# Regulador5V.net
KiCad netlist of a schematic drawn in Altium Designer
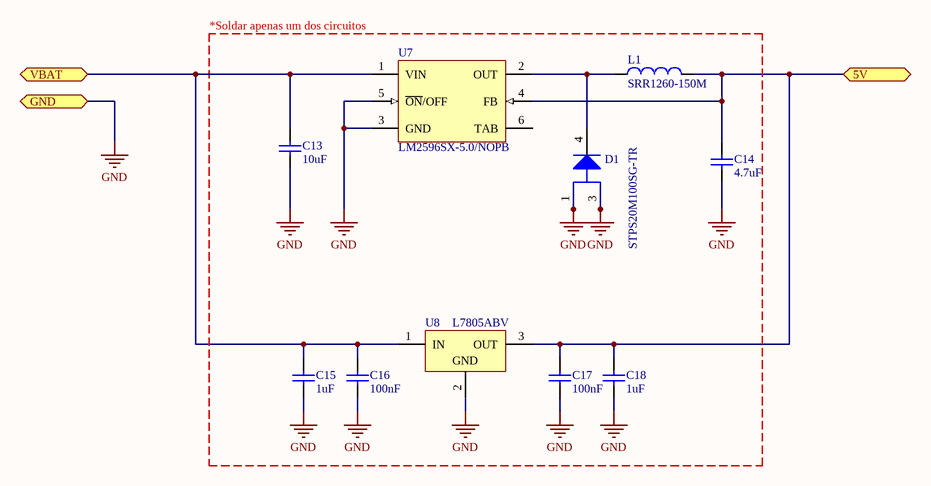
[diagram p0: Regulador5V.SchDoc]

(export (version "E")
  (design (tool "Eeschema 10.0.6"))
  (components
    (comp (ref "C13")
      (value "10uF")
      (footprint "CAPC1206(3216)190_N")
      (description "CAP 10uF 50V ±20% 1206 (3216 Metric) Thickness 1.9mm SMD")
      (fields (field (name "TOLERANCE") "Â±20%"))
      (libsource (lib "Altium Content Vault") (part "CAP"))
    )
    (comp (ref "C14")
      (value "4.7uF")
      (footprint "CAPC0805(2012)145_N")
      (description "CAP 4.7uF 25V ±20% 0805 (2012 Metric) Thickness 1.45mm SMD")
      (fields (field (name "TOLERANCE") "Â±20%"))
      (libsource (lib "Altium Content Vault") (part "CAP"))
    )
    (comp (ref "C15")
      (value "1uF")
      (footprint "CAPC0805(2012)145_L")
      (description "CAP 1uF 50V ±10% 0805 (2012 Metric) Thickness 1.45mm SMD")
      (fields (field (name "TOLERANCE") "Â±10%"))
      (libsource (lib "Altium Content Vault") (part "CAP"))
    )
    (comp (ref "C16")
      (value "100nF")
      (footprint "CAPC0805(2012)145_N")
      (description "CAP 100nF 50V ±5% 0805 (2012 Metric) Thickness 1.45mm SMD")
      (fields (field (name "TOLERANCE") "Â±5%"))
      (libsource (lib "Altium Content Vault") (part "CAP"))
    )
    (comp (ref "C17")
      (value "100nF")
      (footprint "CAPC0805(2012)145_N")
      (description "CAP 100nF 50V ±5% 0805 (2012 Metric) Thickness 1.45mm SMD")
      (fields (field (name "TOLERANCE") "Â±5%"))
      (libsource (lib "Altium Content Vault") (part "CAP"))
    )
    (comp (ref "C18")
      (value "1uF")
      (footprint "CAPC0805(2012)145_L")
      (description "CAP 1uF 50V ±10% 0805 (2012 Metric) Thickness 1.45mm SMD")
      (fields (field (name "TOLERANCE") "Â±10%"))
      (libsource (lib "Altium Content Vault") (part "CAP"))
    )
    (comp (ref "D1")
      (value "STPS20M100SG-TR")
      (footprint "ONSC-D2PAK-3-418B-04_J_V")
      (description "SWITCHMODE(TM) Power Rectifier ORing Function Diode, 3-Pin D2PAK, Tape and Reel")
      (fields (field (name "MANUFACTURER") "On Semiconductor"))
      (libsource (lib "Diodo D2PAK") (part "CMP-1055-00080-1"))
    )
    (comp (ref "L1")
      (value "SRR1260-150M")
      (footprint "BOUR-SRR1260_V")
      (description "Shielded Power Inductor, 15 uH, +/- 20%, -40 to 125 degC, 2-Pin SMD, RoHS, Tape and Reel")
      (fields (field (name "MANUFACTURER") "Bourns") (field (name "TOLERANCE") "20%"))
      (libsource (lib "Altium Content Vault") (part "IND-2"))
    )
    (comp (ref "U7")
      (value "LM2596SX-5.0/NOPB")
      (footprint "TS5B_M")
      (description "SIMPLE SWITCHER® Power Converter 150 KHz 3A Step-Down Voltage Regulator, 5-pin TO-263")
      (fields (field (name "MANUFACTURER") "Texas Instruments"))
      (libsource (lib "LM2596SX-5.0") (part "CMP-0069-00282-2"))
    )
    (comp (ref "U8")
      (value "L7805ABV")
      (footprint "TO220")
      (description "Positive Voltage Regulator, 5V, 3-Pin TO-220")
      (libsource (lib "Altium Content Vault") (part "PM-REG-L4940-SIL3"))
    )
  )
  (nets
    (net (code "1") (name "/5V") (class "Default")
      (node (ref "C14") (pin "2") (pinfunction "2_2") (pintype "passive"))
      (node (ref "C17") (pin "2") (pinfunction "2_2") (pintype "passive"))
      (node (ref "C18") (pin "2") (pinfunction "2_2") (pintype "passive"))
      (node (ref "L1") (pin "2") (pinfunction "2_2") (pintype "passive"))
      (node (ref "U7") (pin "4") (pinfunction "FB_4") (pintype "input"))
      (node (ref "U8") (pin "3") (pinfunction "OUT_3") (pintype "power_in"))
    )
    (net (code "2") (name "/VBAT") (class "Default")
      (node (ref "C13") (pin "2") (pinfunction "2_2") (pintype "passive"))
      (node (ref "C15") (pin "2") (pinfunction "2_2") (pintype "passive"))
      (node (ref "C16") (pin "2") (pinfunction "2_2") (pintype "passive"))
      (node (ref "U7") (pin "1") (pinfunction "VIN_1") (pintype "power_in"))
      (node (ref "U8") (pin "1") (pinfunction "IN_1") (pintype "power_in"))
    )
    (net (code "3") (name "GND") (class "Default")
      (node (ref "C13") (pin "1") (pinfunction "1_1") (pintype "passive"))
      (node (ref "C14") (pin "1") (pinfunction "1_1") (pintype "passive"))
      (node (ref "C15") (pin "1") (pinfunction "1_1") (pintype "passive"))
      (node (ref "C16") (pin "1") (pinfunction "1_1") (pintype "passive"))
      (node (ref "C17") (pin "1") (pinfunction "1_1") (pintype "passive"))
      (node (ref "C18") (pin "1") (pinfunction "1_1") (pintype "passive"))
      (node (ref "D1") (pin "1") (pinfunction "A_1") (pintype "passive"))
      (node (ref "D1") (pin "3") (pinfunction "A_3") (pintype "passive"))
      (node (ref "U7") (pin "3") (pinfunction "GND_3") (pintype "power_in"))
      (node (ref "U7") (pin "5") (pinfunction "~{ON}/OFF_5") (pintype "input"))
      (node (ref "U8") (pin "2") (pinfunction "GND_2") (pintype "power_in"))
    )
    (net (code "4") (name "Net-(D1-K)") (class "Default")
      (node (ref "D1") (pin "4") (pinfunction "K_4") (pintype "passive"))
      (node (ref "L1") (pin "1") (pinfunction "1_1") (pintype "passive"))
      (node (ref "U7") (pin "2") (pinfunction "OUT_2") (pintype "power_in"))
    )
    (net (code "5") (name "unconnected-(U7-TAB-Pad6)") (class "Default")
      (node (ref "U7") (pin "6") (pinfunction "TAB_6") (pintype "power_in"))
    )
  )
)
